# CPU_v3_1.net
KiCad netlist of a schematic drawn in EAGLE
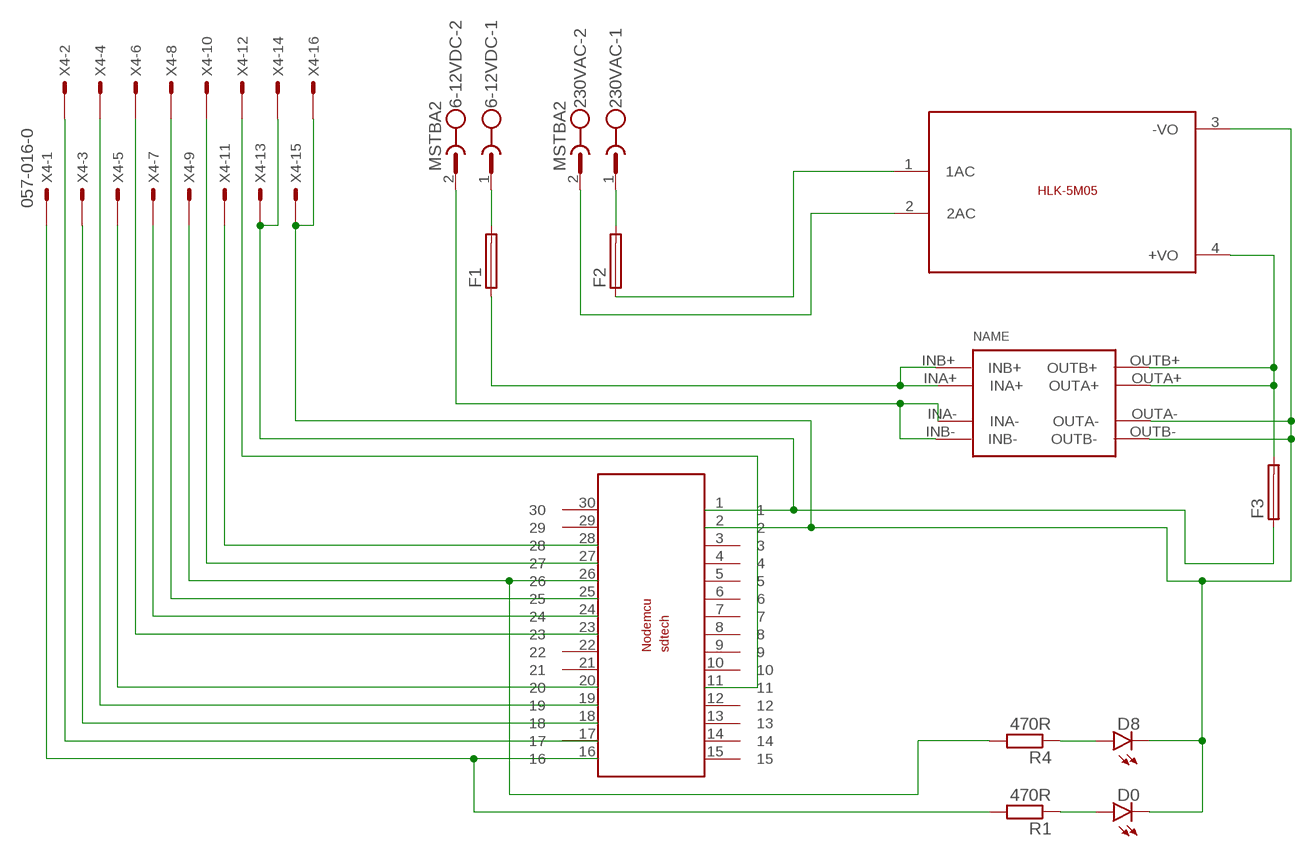
[diagram p0: schematic, sheet 1]

(export (version "E")
  (design (tool "Eeschema 10.0.6"))
  (components
    (comp (ref "6-12VDC")
      (value "MSTBA2")
      (footprint "eagle-import:MSTBA2")
      (fields (field (name "MF") "FARNELL") (field (name "MPN") "1757242"))
      (libsource (lib "eagle-import") (part "MSTBA2"))
    )
    (comp (ref "230VAC")
      (value "MSTBA2")
      (footprint "eagle-import:MSTBA2")
      (fields (field (name "MF") "FARNELL") (field (name "MPN") "1757242"))
      (libsource (lib "eagle-import") (part "MSTBA2"))
    )
    (comp (ref "D0")
      (value "LED3MM")
      (footprint "eagle-import:LED3MM")
      (libsource (lib "eagle-import") (part "LED3MM"))
    )
    (comp (ref "D8")
      (value "LED3MM")
      (footprint "eagle-import:LED3MM")
      (libsource (lib "eagle-import") (part "LED3MM"))
    )
    (comp (ref "F1")
      (value "SH22,5A")
      (footprint "eagle-import:SH22,5A")
      (fields (field (name "MPN") "0031.7701.11"))
      (libsource (lib "eagle-import") (part "SH22,5A"))
    )
    (comp (ref "F2")
      (value "SH22,5A")
      (footprint "eagle-import:SH22,5A")
      (fields (field (name "MPN") "0031.7701.11"))
      (libsource (lib "eagle-import") (part "SH22,5A"))
    )
    (comp (ref "F3")
      (value "SH22,5A")
      (footprint "eagle-import:SH22,5A")
      (fields (field (name "MPN") "0031.7701.11"))
      (libsource (lib "eagle-import") (part "SH22,5A"))
    )
    (comp (ref "R1")
      (value "470R")
      (footprint "eagle-import:0309_10")
      (libsource (lib "eagle-import") (part "R-EU_0309/10"))
    )
    (comp (ref "R4")
      (value "470R")
      (footprint "eagle-import:0309_10")
      (libsource (lib "eagle-import") (part "R-EU_0309/10"))
    )
    (comp (ref "U$1")
      (value "NODEMCUESP8266")
      (footprint "eagle-import:NODEMCUESP8266")
      (fields (field (name "SPICEPREFIX") "X"))
      (libsource (lib "eagle-import") (part "NODEMCUESP8266"))
    )
    (comp (ref "U$2")
      (value "CP8-ADJ-B")
      (footprint "eagle-import:CP8-ADJ-B")
      (libsource (lib "eagle-import") (part "CP8-ADJ-B"))
    )
    (comp (ref "U$3")
      (value "5VDC/5W")
      (footprint "eagle-import:HLK-5M05")
      (libsource (lib "eagle-import") (part "HLK-5M05"))
    )
    (comp (ref "X4")
      (value "057-016-0")
      (footprint "eagle-import:057-016-0")
      (libsource (lib "eagle-import") (part "057-016-0"))
    )
  )
  (nets
    (net (code "1") (name "Net-(6-12VDC-Pad1)") (class "Default")
      (node (ref "6-12VDC") (pin "1") (pinfunction "1_1") (pintype "passive"))
      (node (ref "F1") (pin "2") (pinfunction "2_2") (pintype "passive"))
    )
    (net (code "2") (name "Net-(6-12VDCB-1)") (class "Default")
      (node (ref "6-12VDC") (pin "2") (pinfunction "1_2") (pintype "passive"))
      (node (ref "U$2") (pin "INA-") (pinfunction "INA-_INA-") (pintype "passive"))
      (node (ref "U$2") (pin "INB-") (pinfunction "INB-_INB-") (pintype "passive"))
    )
    (net (code "3") (name "Net-(230VAC-Pad1)") (class "Default")
      (node (ref "230VAC") (pin "1") (pinfunction "1_1") (pintype "passive"))
      (node (ref "F2") (pin "2") (pinfunction "2_2") (pintype "passive"))
    )
    (net (code "4") (name "Net-(230VACB-1)") (class "Default")
      (node (ref "230VAC") (pin "2") (pinfunction "1_2") (pintype "passive"))
      (node (ref "U$3") (pin "2") (pinfunction "2AC_2") (pintype "bidirectional"))
    )
    (net (code "5") (name "Net-(D0-C)") (class "Default")
      (node (ref "D0") (pin "K") (pinfunction "C_K") (pintype "passive"))
      (node (ref "D8") (pin "K") (pinfunction "C_K") (pintype "passive"))
      (node (ref "U$1") (pin "2") (pinfunction "2_2") (pintype "bidirectional"))
      (node (ref "U$2") (pin "OUTA-") (pinfunction "OUTA-_OUTA-") (pintype "passive"))
      (node (ref "U$2") (pin "OUTB-") (pinfunction "OUTB-_OUTB-") (pintype "bidirectional"))
      (node (ref "U$3") (pin "3") (pinfunction "-VO_3") (pintype "bidirectional"))
      (node (ref "X4") (pin "15") (pinfunction "S_15") (pintype "passive"))
      (node (ref "X4") (pin "16") (pinfunction "S_16") (pintype "passive"))
    )
    (net (code "6") (name "Net-(D0-PadA)") (class "Default")
      (node (ref "D0") (pin "A") (pinfunction "A_A") (pintype "passive"))
      (node (ref "R1") (pin "1") (pinfunction "1_1") (pintype "passive"))
    )
    (net (code "7") (name "Net-(D8-PadA)") (class "Default")
      (node (ref "D8") (pin "A") (pinfunction "A_A") (pintype "passive"))
      (node (ref "R4") (pin "1") (pinfunction "1_1") (pintype "passive"))
    )
    (net (code "8") (name "Net-(F1-Pad1)") (class "Default")
      (node (ref "F1") (pin "1") (pinfunction "1_1") (pintype "passive"))
      (node (ref "U$2") (pin "INA+") (pinfunction "INA+_INA+") (pintype "passive"))
      (node (ref "U$2") (pin "INB+") (pinfunction "INB+_INB+") (pintype "passive"))
    )
    (net (code "9") (name "Net-(U$3-+VO)") (class "Default")
      (node (ref "F3") (pin "2") (pinfunction "2_2") (pintype "passive"))
      (node (ref "U$2") (pin "OUTA+") (pinfunction "OUTA+_OUTA+") (pintype "passive"))
      (node (ref "U$2") (pin "OUTB+") (pinfunction "OUTB+_OUTB+") (pintype "passive"))
      (node (ref "U$3") (pin "4") (pinfunction "+VO_4") (pintype "bidirectional"))
    )
    (net (code "10") (name "Net-(U$3-1AC)") (class "Default")
      (node (ref "F2") (pin "1") (pinfunction "1_1") (pintype "passive"))
      (node (ref "U$3") (pin "1") (pinfunction "1AC_1") (pintype "bidirectional"))
    )
    (net (code "11") (name "Net-(X4A-S)") (class "Default")
      (node (ref "R1") (pin "2") (pinfunction "2_2") (pintype "passive"))
      (node (ref "U$1") (pin "16") (pinfunction "16_16") (pintype "bidirectional"))
      (node (ref "X4") (pin "1") (pinfunction "S_1") (pintype "passive"))
    )
    (net (code "12") (name "Net-(X4B-S)") (class "Default")
      (node (ref "U$1") (pin "27") (pinfunction "27_27") (pintype "bidirectional"))
      (node (ref "X4") (pin "10") (pinfunction "S_10") (pintype "passive"))
    )
    (net (code "13") (name "Net-(X4C-S)") (class "Default")
      (node (ref "U$1") (pin "28") (pinfunction "28_28") (pintype "bidirectional"))
      (node (ref "X4") (pin "11") (pinfunction "S_11") (pintype "passive"))
    )
    (net (code "14") (name "Net-(X4D-S)") (class "Default")
      (node (ref "U$1") (pin "11") (pinfunction "11_11") (pintype "bidirectional"))
      (node (ref "X4") (pin "12") (pinfunction "S_12") (pintype "passive"))
    )
    (net (code "15") (name "Net-(X4E-S)") (class "Default")
      (node (ref "F3") (pin "1") (pinfunction "1_1") (pintype "passive"))
      (node (ref "U$1") (pin "1") (pinfunction "1_1") (pintype "bidirectional"))
      (node (ref "X4") (pin "13") (pinfunction "S_13") (pintype "passive"))
      (node (ref "X4") (pin "14") (pinfunction "S_14") (pintype "passive"))
    )
    (net (code "16") (name "Net-(X4I-S)") (class "Default")
      (node (ref "U$1") (pin "17") (pinfunction "17_17") (pintype "bidirectional"))
      (node (ref "X4") (pin "2") (pinfunction "S_2") (pintype "passive"))
    )
    (net (code "17") (name "Net-(X4J-S)") (class "Default")
      (node (ref "U$1") (pin "18") (pinfunction "18_18") (pintype "bidirectional"))
      (node (ref "X4") (pin "3") (pinfunction "S_3") (pintype "passive"))
    )
    (net (code "18") (name "Net-(X4K-S)") (class "Default")
      (node (ref "U$1") (pin "19") (pinfunction "19_19") (pintype "bidirectional"))
      (node (ref "X4") (pin "4") (pinfunction "S_4") (pintype "passive"))
    )
    (net (code "19") (name "Net-(X4L-S)") (class "Default")
      (node (ref "U$1") (pin "20") (pinfunction "20_20") (pintype "bidirectional"))
      (node (ref "X4") (pin "5") (pinfunction "S_5") (pintype "passive"))
    )
    (net (code "20") (name "Net-(X4M-S)") (class "Default")
      (node (ref "U$1") (pin "23") (pinfunction "23_23") (pintype "bidirectional"))
      (node (ref "X4") (pin "6") (pinfunction "S_6") (pintype "passive"))
    )
    (net (code "21") (name "Net-(X4N-S)") (class "Default")
      (node (ref "U$1") (pin "24") (pinfunction "24_24") (pintype "bidirectional"))
      (node (ref "X4") (pin "7") (pinfunction "S_7") (pintype "passive"))
    )
    (net (code "22") (name "Net-(X4O-S)") (class "Default")
      (node (ref "U$1") (pin "25") (pinfunction "25_25") (pintype "bidirectional"))
      (node (ref "X4") (pin "8") (pinfunction "S_8") (pintype "passive"))
    )
    (net (code "23") (name "Net-(X4P-S)") (class "Default")
      (node (ref "R4") (pin "2") (pinfunction "2_2") (pintype "passive"))
      (node (ref "U$1") (pin "26") (pinfunction "26_26") (pintype "bidirectional"))
      (node (ref "X4") (pin "9") (pinfunction "S_9") (pintype "passive"))
    )
    (net (code "24") (name "unconnected-(U$1-Pad3)") (class "Default")
      (node (ref "U$1") (pin "3") (pinfunction "3_3") (pintype "bidirectional"))
    )
    (net (code "25") (name "unconnected-(U$1-Pad4)") (class "Default")
      (node (ref "U$1") (pin "4") (pinfunction "4_4") (pintype "bidirectional"))
    )
    (net (code "26") (name "unconnected-(U$1-Pad5)") (class "Default")
      (node (ref "U$1") (pin "5") (pinfunction "5_5") (pintype "bidirectional"))
    )
    (net (code "27") (name "unconnected-(U$1-Pad6)") (class "Default")
      (node (ref "U$1") (pin "6") (pinfunction "6_6") (pintype "bidirectional"))
    )
    (net (code "28") (name "unconnected-(U$1-Pad7)") (class "Default")
      (node (ref "U$1") (pin "7") (pinfunction "7_7") (pintype "bidirectional"))
    )
    (net (code "29") (name "unconnected-(U$1-Pad8)") (class "Default")
      (node (ref "U$1") (pin "8") (pinfunction "8_8") (pintype "bidirectional"))
    )
    (net (code "30") (name "unconnected-(U$1-Pad9)") (class "Default")
      (node (ref "U$1") (pin "9") (pinfunction "9_9") (pintype "bidirectional"))
    )
    (net (code "31") (name "unconnected-(U$1-Pad10)") (class "Default")
      (node (ref "U$1") (pin "10") (pinfunction "10_10") (pintype "bidirectional"))
    )
    (net (code "32") (name "unconnected-(U$1-Pad12)") (class "Default")
      (node (ref "U$1") (pin "12") (pinfunction "12_12") (pintype "bidirectional"))
    )
    (net (code "33") (name "unconnected-(U$1-Pad13)") (class "Default")
      (node (ref "U$1") (pin "13") (pinfunction "13_13") (pintype "bidirectional"))
    )
    (net (code "34") (name "unconnected-(U$1-Pad14)") (class "Default")
      (node (ref "U$1") (pin "14") (pinfunction "14_14") (pintype "bidirectional"))
    )
    (net (code "35") (name "unconnected-(U$1-Pad15)") (class "Default")
      (node (ref "U$1") (pin "15") (pinfunction "15_15") (pintype "bidirectional"))
    )
    (net (code "36") (name "unconnected-(U$1-Pad21)") (class "Default")
      (node (ref "U$1") (pin "21") (pinfunction "21_21") (pintype "bidirectional"))
    )
    (net (code "37") (name "unconnected-(U$1-Pad22)") (class "Default")
      (node (ref "U$1") (pin "22") (pinfunction "22_22") (pintype "bidirectional"))
    )
    (net (code "38") (name "unconnected-(U$1-Pad29)") (class "Default")
      (node (ref "U$1") (pin "29") (pinfunction "29_29") (pintype "bidirectional"))
    )
    (net (code "39") (name "unconnected-(U$1-Pad30)") (class "Default")
      (node (ref "U$1") (pin "30") (pinfunction "30_30") (pintype "bidirectional"))
    )
  )
)
